# internal_excitation_2_w_gp_v1_1.net
KiCad netlist of a schematic drawn in EAGLE
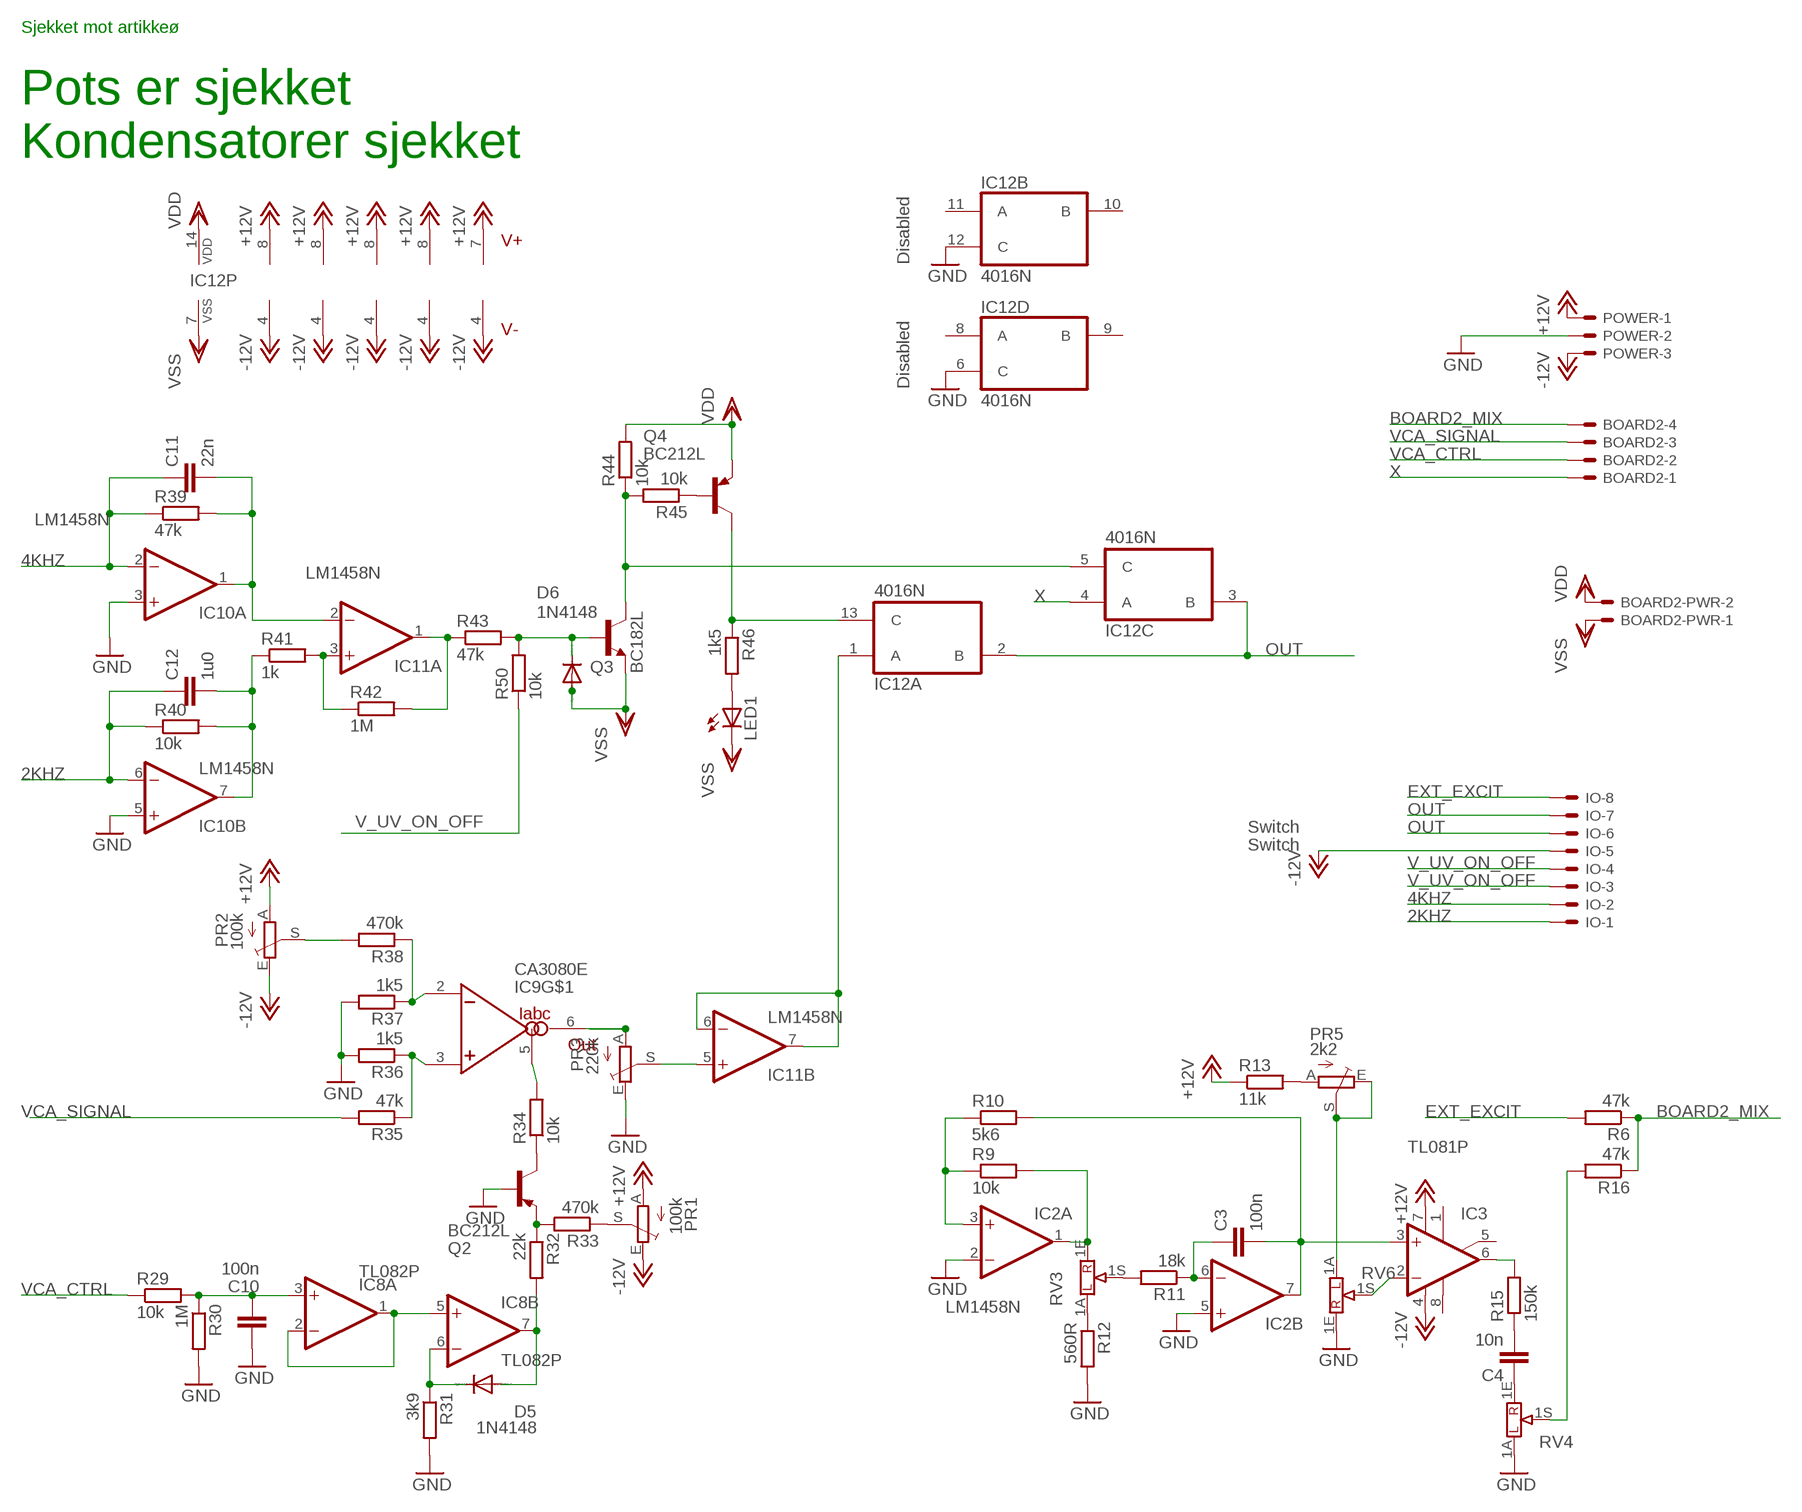
[diagram p0: schematic, sheet 1]

(export (version "E")
  (design (tool "Eeschema 10.0.6"))
  (components
    (comp (ref "BOARD2")
      (value "22-23-2041")
      (footprint "eagle-import:22-23-2041")
      (fields (field (name "MF") "MOLEX"))
      (libsource (lib "eagle-import") (part "22-23-2041"))
    )
    (comp (ref "BOARD2-PWR")
      (value "22-23-2021")
      (footprint "eagle-import:22-23-2021")
      (fields (field (name "MF") "MOLEX"))
      (libsource (lib "eagle-import") (part "22-23-2021"))
    )
    (comp (ref "C3")
      (value "100n")
      (footprint "eagle-import:C050-030X075")
      (libsource (lib "eagle-import") (part "C-EU050-030X075"))
    )
    (comp (ref "C4")
      (value "10n")
      (footprint "eagle-import:C025-025X050")
      (libsource (lib "eagle-import") (part "C-EU025-025X050"))
    )
    (comp (ref "C10")
      (value "100n")
      (footprint "eagle-import:C050-030X075")
      (libsource (lib "eagle-import") (part "C-EU050-030X075"))
    )
    (comp (ref "C11")
      (value "22n")
      (footprint "eagle-import:C050-030X075")
      (libsource (lib "eagle-import") (part "C-EU050-030X075"))
    )
    (comp (ref "C12")
      (value "1u0")
      (footprint "eagle-import:C050-030X075")
      (libsource (lib "eagle-import") (part "C-EU050-030X075"))
    )
    (comp (ref "D5")
      (value "1N4148")
      (footprint "eagle-import:DO35-5J")
      (libsource (lib "eagle-import") (part "1N4148DOJ35-5"))
    )
    (comp (ref "D6")
      (value "1N4148")
      (footprint "eagle-import:DO35-5J")
      (libsource (lib "eagle-import") (part "1N4148DOJ35-5"))
    )
    (comp (ref "IC2")
      (value "LM1458N")
      (footprint "eagle-import:DIL08")
      (libsource (lib "eagle-import") (part "1458NLM"))
    )
    (comp (ref "IC3")
      (value "TL081P")
      (footprint "eagle-import:DIL08")
      (libsource (lib "eagle-import") (part "TL081P"))
    )
    (comp (ref "IC8")
      (value "TL082P")
      (footprint "eagle-import:DIL08")
      (libsource (lib "eagle-import") (part "TL082P"))
    )
    (comp (ref "IC9")
      (value "CA3080E")
      (footprint "eagle-import:DIL08")
      (libsource (lib "eagle-import") (part "CA3080E"))
    )
    (comp (ref "IC10")
      (value "LM1458N")
      (footprint "eagle-import:DIL08")
      (libsource (lib "eagle-import") (part "1458NLM"))
    )
    (comp (ref "IC11")
      (value "LM1458N")
      (footprint "eagle-import:DIL08")
      (libsource (lib "eagle-import") (part "1458NLM"))
    )
    (comp (ref "IC12")
      (value "4016N")
      (footprint "eagle-import:DIL14")
      (libsource (lib "eagle-import") (part "4016N"))
    )
    (comp (ref "IO")
      (value "22-23-2081")
      (footprint "eagle-import:22-23-2081")
      (fields (field (name "MF") "MOLEX"))
      (libsource (lib "eagle-import") (part "22-23-2081"))
    )
    (comp (ref "LED1")
      (value "LED3MM")
      (footprint "eagle-import:LED3MM")
      (libsource (lib "eagle-import") (part "LED3MM"))
    )
    (comp (ref "POWER")
      (value "KK-156-3")
      (footprint "eagle-import:KK-156-3")
      (libsource (lib "eagle-import") (part "KK-156-3"))
    )
    (comp (ref "PR1")
      (value "100k")
      (footprint "eagle-import:CA9V")
      (libsource (lib "eagle-import") (part "TRIM_EU-CA9V"))
    )
    (comp (ref "PR2")
      (value "100k")
      (footprint "eagle-import:CA9V")
      (libsource (lib "eagle-import") (part "TRIM_EU-CA9V"))
    )
    (comp (ref "PR3")
      (value "220k")
      (footprint "eagle-import:CA9V")
      (libsource (lib "eagle-import") (part "TRIM_EU-CA9V"))
    )
    (comp (ref "PR5")
      (value "2k2")
      (footprint "eagle-import:CA9V")
      (libsource (lib "eagle-import") (part "TRIM_EU-CA9V"))
    )
    (comp (ref "Q2")
      (value "BC212L")
      (footprint "eagle-import:TO92-CBE")
      (libsource (lib "eagle-import") (part "-PNP-TO92-CBEBF493S"))
    )
    (comp (ref "Q3")
      (value "BC182L")
      (footprint "eagle-import:TO92-ECB")
      (libsource (lib "eagle-import") (part "-NPN-TO92-ECB"))
    )
    (comp (ref "Q4")
      (value "BC212L")
      (footprint "eagle-import:TO92-CBE")
      (libsource (lib "eagle-import") (part "-PNP-TO92-CBEBF493S"))
    )
    (comp (ref "R6")
      (value "47k")
      (footprint "eagle-import:0207_10")
      (libsource (lib "eagle-import") (part "R-EU_0207/10"))
    )
    (comp (ref "R9")
      (value "10k")
      (footprint "eagle-import:0207_7")
      (libsource (lib "eagle-import") (part "R-EU_0207/7"))
    )
    (comp (ref "R10")
      (value "5k6")
      (footprint "eagle-import:0207_7")
      (libsource (lib "eagle-import") (part "R-EU_0207/7"))
    )
    (comp (ref "R11")
      (value "18k")
      (footprint "eagle-import:0207_7")
      (libsource (lib "eagle-import") (part "R-EU_0207/7"))
    )
    (comp (ref "R12")
      (value "560R")
      (footprint "eagle-import:0207_7")
      (libsource (lib "eagle-import") (part "R-EU_0207/7"))
    )
    (comp (ref "R13")
      (value "11k")
      (footprint "eagle-import:0207_7")
      (libsource (lib "eagle-import") (part "R-EU_0207/7"))
    )
    (comp (ref "R15")
      (value "150k")
      (footprint "eagle-import:0207_7")
      (libsource (lib "eagle-import") (part "R-EU_0207/7"))
    )
    (comp (ref "R16")
      (value "47k")
      (footprint "eagle-import:0207_7")
      (libsource (lib "eagle-import") (part "R-EU_0207/7"))
    )
    (comp (ref "R29")
      (value "10k")
      (footprint "eagle-import:0207_7")
      (libsource (lib "eagle-import") (part "R-EU_0207/7"))
    )
    (comp (ref "R30")
      (value "1M")
      (footprint "eagle-import:0207_7")
      (libsource (lib "eagle-import") (part "R-EU_0207/7"))
    )
    (comp (ref "R31")
      (value "3k9")
      (footprint "eagle-import:0207_7")
      (libsource (lib "eagle-import") (part "R-EU_0207/7"))
    )
    (comp (ref "R32")
      (value "22k")
      (footprint "eagle-import:0207_7")
      (libsource (lib "eagle-import") (part "R-EU_0207/7"))
    )
    (comp (ref "R33")
      (value "470k")
      (footprint "eagle-import:0207_7")
      (libsource (lib "eagle-import") (part "R-EU_0207/7"))
    )
    (comp (ref "R34")
      (value "10k")
      (footprint "eagle-import:0207_7")
      (libsource (lib "eagle-import") (part "R-EU_0207/7"))
    )
    (comp (ref "R35")
      (value "47k")
      (footprint "eagle-import:0207_7")
      (libsource (lib "eagle-import") (part "R-EU_0207/7"))
    )
    (comp (ref "R36")
      (value "1k5")
      (footprint "eagle-import:0207_7")
      (libsource (lib "eagle-import") (part "R-EU_0207/7"))
    )
    (comp (ref "R37")
      (value "1k5")
      (footprint "eagle-import:0207_7")
      (libsource (lib "eagle-import") (part "R-EU_0207/7"))
    )
    (comp (ref "R38")
      (value "470k")
      (footprint "eagle-import:0207_7")
      (libsource (lib "eagle-import") (part "R-EU_0207/7"))
    )
    (comp (ref "R39")
      (value "47k")
      (footprint "eagle-import:0207_7")
      (libsource (lib "eagle-import") (part "R-EU_0207/7"))
    )
    (comp (ref "R40")
      (value "10k")
      (footprint "eagle-import:0207_7")
      (libsource (lib "eagle-import") (part "R-EU_0207/7"))
    )
    (comp (ref "R41")
      (value "1k")
      (footprint "eagle-import:0207_7")
      (libsource (lib "eagle-import") (part "R-EU_0207/7"))
    )
    (comp (ref "R42")
      (value "1M")
      (footprint "eagle-import:0207_7")
      (libsource (lib "eagle-import") (part "R-EU_0207/7"))
    )
    (comp (ref "R43")
      (value "47k")
      (footprint "eagle-import:0207_7")
      (libsource (lib "eagle-import") (part "R-EU_0207/7"))
    )
    (comp (ref "R44")
      (value "10k")
      (footprint "eagle-import:0207_7")
      (libsource (lib "eagle-import") (part "R-EU_0207/7"))
    )
    (comp (ref "R45")
      (value "10k")
      (footprint "eagle-import:0207_7")
      (libsource (lib "eagle-import") (part "R-EU_0207/7"))
    )
    (comp (ref "R46")
      (value "1k5")
      (footprint "eagle-import:0207_7")
      (libsource (lib "eagle-import") (part "R-EU_0207/7"))
    )
    (comp (ref "R50")
      (value "10k")
      (footprint "eagle-import:0207_7")
      (libsource (lib "eagle-import") (part "R-EU_0207/7"))
    )
    (comp (ref "RV3")
      (value "10k log")
      (footprint "eagle-import:POT16_W_BRACKET")
      (libsource (lib "eagle-import") (part "POT16_W_BRACKET{dblquote}{dblquote}"))
    )
    (comp (ref "RV4")
      (value "10k log")
      (footprint "eagle-import:POT16_W_BRACKET")
      (libsource (lib "eagle-import") (part "POT16_W_BRACKET{dblquote}{dblquote}"))
    )
    (comp (ref "RV6")
      (value "10k")
      (footprint "eagle-import:POT16_W_BRACKET")
      (libsource (lib "eagle-import") (part "POT16_W_BRACKET{dblquote}{dblquote}"))
    )
  )
  (nets
    (net (code "1") (name "+12V") (class "Default")
      (node (ref "IC10") (pin "8") (pinfunction "V+_8") (pintype "power_in"))
      (node (ref "IC11") (pin "8") (pinfunction "V+_8") (pintype "power_in"))
      (node (ref "IC2") (pin "8") (pinfunction "V+_8") (pintype "power_in"))
      (node (ref "IC3") (pin "7") (pinfunction "V+_7") (pintype "power_in"))
      (node (ref "IC8") (pin "8") (pinfunction "V+_8") (pintype "power_in"))
      (node (ref "IC9") (pin "7") (pinfunction "V+_7") (pintype "bidirectional"))
      (node (ref "POWER") (pin "1") (pinfunction "S_1") (pintype "passive"))
      (node (ref "PR1") (pin "A") (pinfunction "A_A") (pintype "passive"))
      (node (ref "PR2") (pin "A") (pinfunction "A_A") (pintype "passive"))
      (node (ref "R13") (pin "1") (pinfunction "1_1") (pintype "passive"))
    )
    (net (code "2") (name "-12V") (class "Default")
      (node (ref "IC10") (pin "4") (pinfunction "V-_4") (pintype "power_in"))
      (node (ref "IC11") (pin "4") (pinfunction "V-_4") (pintype "power_in"))
      (node (ref "IC2") (pin "4") (pinfunction "V-_4") (pintype "power_in"))
      (node (ref "IC3") (pin "4") (pinfunction "V-_4") (pintype "power_in"))
      (node (ref "IC8") (pin "4") (pinfunction "V-_4") (pintype "power_in"))
      (node (ref "IC9") (pin "4") (pinfunction "V-_4") (pintype "bidirectional"))
      (node (ref "IO") (pin "5") (pinfunction "S_5") (pintype "passive"))
      (node (ref "POWER") (pin "3") (pinfunction "S_3") (pintype "passive"))
      (node (ref "PR1") (pin "E") (pinfunction "E_E") (pintype "passive"))
      (node (ref "PR2") (pin "E") (pinfunction "E_E") (pintype "passive"))
    )
    (net (code "3") (name "/2KHZ") (class "Default")
      (node (ref "C12") (pin "1") (pinfunction "1_1") (pintype "passive"))
      (node (ref "IC10") (pin "6") (pinfunction "-IN_6") (pintype "input"))
      (node (ref "IO") (pin "1") (pinfunction "S_1") (pintype "passive"))
      (node (ref "R40") (pin "1") (pinfunction "1_1") (pintype "passive"))
    )
    (net (code "4") (name "/4KHZ") (class "Default")
      (node (ref "C11") (pin "1") (pinfunction "1_1") (pintype "passive"))
      (node (ref "IC10") (pin "2") (pinfunction "-IN_2") (pintype "input"))
      (node (ref "IO") (pin "2") (pinfunction "S_2") (pintype "passive"))
      (node (ref "R39") (pin "1") (pinfunction "1_1") (pintype "passive"))
    )
    (net (code "5") (name "/BOARD2_MIX") (class "Default")
      (node (ref "BOARD2") (pin "4") (pinfunction "S_4") (pintype "passive"))
      (node (ref "R16") (pin "1") (pinfunction "1_1") (pintype "passive"))
      (node (ref "R6") (pin "1") (pinfunction "1_1") (pintype "passive"))
    )
    (net (code "6") (name "/EXT_EXCIT") (class "Default")
      (node (ref "IO") (pin "8") (pinfunction "S_8") (pintype "passive"))
      (node (ref "R6") (pin "2") (pinfunction "2_2") (pintype "passive"))
    )
    (net (code "7") (name "/OUT") (class "Default")
      (node (ref "IC12") (pin "2") (pinfunction "B_2") (pintype "tri_state"))
      (node (ref "IC12") (pin "3") (pinfunction "B_3") (pintype "tri_state"))
      (node (ref "IO") (pin "6") (pinfunction "S_6") (pintype "passive"))
      (node (ref "IO") (pin "7") (pinfunction "S_7") (pintype "passive"))
    )
    (net (code "8") (name "/VCA_CTRL") (class "Default")
      (node (ref "BOARD2") (pin "2") (pinfunction "S_2") (pintype "passive"))
      (node (ref "R29") (pin "1") (pinfunction "1_1") (pintype "passive"))
    )
    (net (code "9") (name "/VCA_SIGNAL") (class "Default")
      (node (ref "BOARD2") (pin "3") (pinfunction "S_3") (pintype "passive"))
      (node (ref "R35") (pin "2") (pinfunction "2_2") (pintype "passive"))
    )
    (net (code "10") (name "/V_UV_ON_OFF") (class "Default")
      (node (ref "IO") (pin "3") (pinfunction "S_3") (pintype "passive"))
      (node (ref "IO") (pin "4") (pinfunction "S_4") (pintype "passive"))
      (node (ref "R50") (pin "1") (pinfunction "1_1") (pintype "passive"))
    )
    (net (code "11") (name "/X") (class "Default")
      (node (ref "BOARD2") (pin "1") (pinfunction "S_1") (pintype "passive"))
      (node (ref "IC12") (pin "4") (pinfunction "A_4") (pintype "tri_state"))
    )
    (net (code "12") (name "GND") (class "Default")
      (node (ref "C10") (pin "1") (pinfunction "1_1") (pintype "passive"))
      (node (ref "IC10") (pin "3") (pinfunction "+IN_3") (pintype "input"))
      (node (ref "IC10") (pin "5") (pinfunction "+IN_5") (pintype "input"))
      (node (ref "IC12") (pin "12") (pinfunction "C_12") (pintype "input"))
      (node (ref "IC12") (pin "6") (pinfunction "C_6") (pintype "input"))
      (node (ref "IC2") (pin "2") (pinfunction "-IN_2") (pintype "input"))
      (node (ref "IC2") (pin "5") (pinfunction "+IN_5") (pintype "input"))
      (node (ref "POWER") (pin "2") (pinfunction "S_2") (pintype "passive"))
      (node (ref "PR3") (pin "E") (pinfunction "E_E") (pintype "passive"))
      (node (ref "Q2") (pin "B") (pinfunction "B_B") (pintype "passive"))
      (node (ref "R12") (pin "2") (pinfunction "2_2") (pintype "passive"))
      (node (ref "R30") (pin "2") (pinfunction "2_2") (pintype "passive"))
      (node (ref "R31") (pin "2") (pinfunction "2_2") (pintype "passive"))
      (node (ref "R36") (pin "2") (pinfunction "2_2") (pintype "passive"))
      (node (ref "R37") (pin "2") (pinfunction "2_2") (pintype "passive"))
      (node (ref "RV4") (pin "1A") (pinfunction "1A_1A") (pintype "passive"))
      (node (ref "RV6") (pin "1E") (pinfunction "1E_1E") (pintype "passive"))
    )
    (net (code "13") (name "Net-(C4-Pad1)") (class "Default")
      (node (ref "C4") (pin "1") (pinfunction "1_1") (pintype "passive"))
      (node (ref "RV4") (pin "1E") (pinfunction "1E_1E") (pintype "passive"))
    )
    (net (code "14") (name "Net-(C4-Pad2)") (class "Default")
      (node (ref "C4") (pin "2") (pinfunction "2_2") (pintype "passive"))
      (node (ref "R15") (pin "1") (pinfunction "1_1") (pintype "passive"))
    )
    (net (code "15") (name "Net-(D6-PadC)") (class "Default")
      (node (ref "D6") (pin "C") (pinfunction "C_C") (pintype "passive"))
      (node (ref "Q3") (pin "B") (pinfunction "B_B") (pintype "passive"))
      (node (ref "R43") (pin "2") (pinfunction "2_2") (pintype "passive"))
      (node (ref "R50") (pin "2") (pinfunction "2_2") (pintype "passive"))
    )
    (net (code "16") (name "Net-(IC2A-+IN)") (class "Default")
      (node (ref "IC2") (pin "3") (pinfunction "+IN_3") (pintype "input"))
      (node (ref "R10") (pin "1") (pinfunction "1_1") (pintype "passive"))
      (node (ref "R9") (pin "1") (pinfunction "1_1") (pintype "passive"))
    )
    (net (code "17") (name "Net-(IC2A-OUT)") (class "Default")
      (node (ref "IC2") (pin "1") (pinfunction "OUT_1") (pintype "output"))
      (node (ref "R9") (pin "2") (pinfunction "2_2") (pintype "passive"))
      (node (ref "RV3") (pin "1E") (pinfunction "1E_1E") (pintype "passive"))
    )
    (net (code "18") (name "Net-(IC2B--IN)") (class "Default")
      (node (ref "C3") (pin "1") (pinfunction "1_1") (pintype "passive"))
      (node (ref "IC2") (pin "6") (pinfunction "-IN_6") (pintype "input"))
      (node (ref "R11") (pin "1") (pinfunction "1_1") (pintype "passive"))
    )
    (net (code "19") (name "Net-(IC2B-OUT)") (class "Default")
      (node (ref "C3") (pin "2") (pinfunction "2_2") (pintype "passive"))
      (node (ref "IC2") (pin "7") (pinfunction "OUT_7") (pintype "output"))
      (node (ref "IC3") (pin "3") (pinfunction "+IN_3") (pintype "input"))
      (node (ref "R10") (pin "2") (pinfunction "2_2") (pintype "passive"))
    )
    (net (code "20") (name "Net-(IC3--IN)") (class "Default")
      (node (ref "IC3") (pin "2") (pinfunction "-IN_2") (pintype "input"))
      (node (ref "RV6") (pin "1S") (pinfunction "1S_1S") (pintype "passive"))
    )
    (net (code "21") (name "Net-(IC3-OUT)") (class "Default")
      (node (ref "IC3") (pin "6") (pinfunction "OUT_6") (pintype "output"))
      (node (ref "R15") (pin "2") (pinfunction "2_2") (pintype "passive"))
    )
    (net (code "22") (name "Net-(IC8A-+IN)") (class "Default")
      (node (ref "C10") (pin "2") (pinfunction "2_2") (pintype "passive"))
      (node (ref "IC8") (pin "3") (pinfunction "+IN_3") (pintype "input"))
      (node (ref "R29") (pin "2") (pinfunction "2_2") (pintype "passive"))
      (node (ref "R30") (pin "1") (pinfunction "1_1") (pintype "passive"))
    )
    (net (code "23") (name "Net-(IC8A--IN)") (class "Default")
      (node (ref "IC8") (pin "1") (pinfunction "OUT_1") (pintype "output"))
      (node (ref "IC8") (pin "2") (pinfunction "-IN_2") (pintype "input"))
      (node (ref "IC8") (pin "5") (pinfunction "+IN_5") (pintype "input"))
    )
    (net (code "24") (name "Net-(IC8B--IN)") (class "Default")
      (node (ref "D5") (pin "C") (pinfunction "C_C") (pintype "passive"))
      (node (ref "IC8") (pin "6") (pinfunction "-IN_6") (pintype "input"))
      (node (ref "R31") (pin "1") (pinfunction "1_1") (pintype "passive"))
    )
    (net (code "25") (name "Net-(IC8B-OUT)") (class "Default")
      (node (ref "D5") (pin "A") (pinfunction "A_A") (pintype "passive"))
      (node (ref "IC8") (pin "7") (pinfunction "OUT_7") (pintype "output"))
      (node (ref "R32") (pin "2") (pinfunction "2_2") (pintype "passive"))
    )
    (net (code "26") (name "Net-(IC9A-+IN)") (class "Default")
      (node (ref "IC9") (pin "3") (pinfunction "+IN_3") (pintype "bidirectional"))
      (node (ref "R35") (pin "1") (pinfunction "1_1") (pintype "passive"))
      (node (ref "R36") (pin "1") (pinfunction "1_1") (pintype "passive"))
    )
    (net (code "27") (name "Net-(IC9A--IN)") (class "Default")
      (node (ref "IC9") (pin "2") (pinfunction "-IN_2") (pintype "bidirectional"))
      (node (ref "R37") (pin "1") (pinfunction "1_1") (pintype "passive"))
      (node (ref "R38") (pin "1") (pinfunction "1_1") (pintype "passive"))
    )
    (net (code "28") (name "Net-(IC9A-IABC)") (class "Default")
      (node (ref "IC9") (pin "5") (pinfunction "IABC_5") (pintype "bidirectional"))
      (node (ref "R34") (pin "2") (pinfunction "2_2") (pintype "passive"))
    )
    (net (code "29") (name "Net-(IC9A-OUT)") (class "Default")
      (node (ref "IC9") (pin "6") (pinfunction "OUT_6") (pintype "bidirectional"))
      (node (ref "PR3") (pin "A") (pinfunction "A_A") (pintype "passive"))
    )
    (net (code "30") (name "Net-(IC10A-OUT)") (class "Default")
      (node (ref "C11") (pin "2") (pinfunction "2_2") (pintype "passive"))
      (node (ref "IC10") (pin "1") (pinfunction "OUT_1") (pintype "output"))
      (node (ref "IC11") (pin "2") (pinfunction "-IN_2") (pintype "input"))
      (node (ref "R39") (pin "2") (pinfunction "2_2") (pintype "passive"))
    )
    (net (code "31") (name "Net-(IC10B-OUT)") (class "Default")
      (node (ref "C12") (pin "2") (pinfunction "2_2") (pintype "passive"))
      (node (ref "IC10") (pin "7") (pinfunction "OUT_7") (pintype "output"))
      (node (ref "R40") (pin "2") (pinfunction "2_2") (pintype "passive"))
      (node (ref "R41") (pin "1") (pinfunction "1_1") (pintype "passive"))
    )
    (net (code "32") (name "Net-(IC11A-+IN)") (class "Default")
      (node (ref "IC11") (pin "3") (pinfunction "+IN_3") (pintype "input"))
      (node (ref "R41") (pin "2") (pinfunction "2_2") (pintype "passive"))
      (node (ref "R42") (pin "1") (pinfunction "1_1") (pintype "passive"))
    )
    (net (code "33") (name "Net-(IC11A-OUT)") (class "Default")
      (node (ref "IC11") (pin "1") (pinfunction "OUT_1") (pintype "output"))
      (node (ref "R42") (pin "2") (pinfunction "2_2") (pintype "passive"))
      (node (ref "R43") (pin "1") (pinfunction "1_1") (pintype "passive"))
    )
    (net (code "34") (name "Net-(IC11B-+IN)") (class "Default")
      (node (ref "IC11") (pin "5") (pinfunction "+IN_5") (pintype "input"))
      (node (ref "PR3") (pin "S") (pinfunction "S_S") (pintype "passive"))
    )
    (net (code "35") (name "Net-(IC11B--IN)") (class "Default")
      (node (ref "IC11") (pin "6") (pinfunction "-IN_6") (pintype "input"))
      (node (ref "IC11") (pin "7") (pinfunction "OUT_7") (pintype "output"))
      (node (ref "IC12") (pin "1") (pinfunction "A_1") (pintype "tri_state"))
    )
    (net (code "36") (name "Net-(IC12A-C)") (class "Default")
      (node (ref "IC12") (pin "13") (pinfunction "C_13") (pintype "input"))
      (node (ref "Q4") (pin "C") (pinfunction "C_C") (pintype "passive"))
      (node (ref "R46") (pin "1") (pinfunction "1_1") (pintype "passive"))
    )
    (net (code "37") (name "Net-(IC12C-C)") (class "Default")
      (node (ref "IC12") (pin "5") (pinfunction "C_5") (pintype "input"))
      (node (ref "Q3") (pin "C") (pinfunction "C_C") (pintype "passive"))
      (node (ref "R44") (pin "1") (pinfunction "1_1") (pintype "passive"))
      (node (ref "R45") (pin "2") (pinfunction "2_2") (pintype "passive"))
    )
    (net (code "38") (name "Net-(LED1-PadA)") (class "Default")
      (node (ref "LED1") (pin "A") (pinfunction "A_A") (pintype "passive"))
      (node (ref "R46") (pin "2") (pinfunction "2_2") (pintype "passive"))
    )
    (net (code "39") (name "Net-(PR1-PadS)") (class "Default")
      (node (ref "PR1") (pin "S") (pinfunction "S_S") (pintype "passive"))
      (node (ref "R33") (pin "1") (pinfunction "1_1") (pintype "passive"))
    )
    (net (code "40") (name "Net-(PR2-PadS)") (class "Default")
      (node (ref "PR2") (pin "S") (pinfunction "S_S") (pintype "passive"))
      (node (ref "R38") (pin "2") (pinfunction "2_2") (pintype "passive"))
    )
    (net (code "41") (name "Net-(PR5-PadA)") (class "Default")
      (node (ref "PR5") (pin "A") (pinfunction "A_A") (pintype "passive"))
      (node (ref "R13") (pin "2") (pinfunction "2_2") (pintype "passive"))
    )
    (net (code "42") (name "Net-(PR5-PadE)") (class "Default")
      (node (ref "PR5") (pin "E") (pinfunction "E_E") (pintype "passive"))
      (node (ref "PR5") (pin "S") (pinfunction "S_S") (pintype "passive"))
      (node (ref "RV6") (pin "1A") (pinfunction "1A_1A") (pintype "passive"))
    )
    (net (code "43") (name "Net-(Q2-PadC)") (class "Default")
      (node (ref "Q2") (pin "C") (pinfunction "C_C") (pintype "passive"))
      (node (ref "R34") (pin "1") (pinfunction "1_1") (pintype "passive"))
    )
    (net (code "44") (name "Net-(Q2-PadE)") (class "Default")
      (node (ref "Q2") (pin "E") (pinfunction "E_E") (pintype "passive"))
      (node (ref "R32") (pin "1") (pinfunction "1_1") (pintype "passive"))
      (node (ref "R33") (pin "2") (pinfunction "2_2") (pintype "passive"))
    )
    (net (code "45") (name "Net-(Q4-PadB)") (class "Default")
      (node (ref "Q4") (pin "B") (pinfunction "B_B") (pintype "passive"))
      (node (ref "R45") (pin "1") (pinfunction "1_1") (pintype "passive"))
    )
    (net (code "46") (name "Net-(R11-Pad2)") (class "Default")
      (node (ref "R11") (pin "2") (pinfunction "2_2") (pintype "passive"))
      (node (ref "RV3") (pin "1S") (pinfunction "1S_1S") (pintype "passive"))
    )
    (net (code "47") (name "Net-(R12-Pad1)") (class "Default")
      (node (ref "R12") (pin "1") (pinfunction "1_1") (pintype "passive"))
      (node (ref "RV3") (pin "1A") (pinfunction "1A_1A") (pintype "passive"))
    )
    (net (code "48") (name "Net-(R16-Pad2)") (class "Default")
      (node (ref "R16") (pin "2") (pinfunction "2_2") (pintype "passive"))
      (node (ref "RV4") (pin "1S") (pinfunction "1S_1S") (pintype "passive"))
    )
    (net (code "49") (name "VDD") (class "Default")
      (node (ref "BOARD2-PWR") (pin "2") (pinfunction "S_2") (pintype "passive"))
      (node (ref "IC12") (pin "14") (pinfunction "VDD_14") (pintype "power_in"))
      (node (ref "Q4") (pin "E") (pinfunction "E_E") (pintype "passive"))
      (node (ref "R44") (pin "2") (pinfunction "2_2") (pintype "passive"))
    )
    (net (code "50") (name "VSS") (class "Default")
      (node (ref "BOARD2-PWR") (pin "1") (pinfunction "S_1") (pintype "passive"))
      (node (ref "D6") (pin "A") (pinfunction "A_A") (pintype "passive"))
      (node (ref "IC12") (pin "7") (pinfunction "VSS_7") (pintype "power_in"))
      (node (ref "LED1") (pin "K") (pinfunction "C_K") (pintype "passive"))
      (node (ref "Q3") (pin "E") (pinfunction "E_E") (pintype "passive"))
    )
    (net (code "51") (name "unconnected-(IC3-ON1-Pad1)") (class "Default")
      (node (ref "IC3") (pin "1") (pinfunction "ON1_1") (pintype "passive"))
    )
    (net (code "52") (name "unconnected-(IC3-ON2-Pad5)") (class "Default")
      (node (ref "IC3") (pin "5") (pinfunction "ON2_5") (pintype "passive"))
    )
    (net (code "53") (name "unconnected-(IC3-OPT-Pad8)") (class "Default")
      (node (ref "IC3") (pin "8") (pinfunction "OPT_8") (pintype "passive"))
    )
    (net (code "54") (name "unconnected-(IC12B-A-Pad11)") (class "Default")
      (node (ref "IC12") (pin "11") (pinfunction "A_11") (pintype "tri_state"))
    )
    (net (code "55") (name "unconnected-(IC12B-B-Pad10)") (class "Default")
      (node (ref "IC12") (pin "10") (pinfunction "B_10") (pintype "tri_state"))
    )
    (net (code "56") (name "unconnected-(IC12D-A-Pad8)") (class "Default")
      (node (ref "IC12") (pin "8") (pinfunction "A_8") (pintype "tri_state"))
    )
    (net (code "57") (name "unconnected-(IC12D-B-Pad9)") (class "Default")
      (node (ref "IC12") (pin "9") (pinfunction "B_9") (pintype "tri_state"))
    )
  )
)
